# -_-V1.net
KiCad netlist of a schematic drawn in Altium Designer
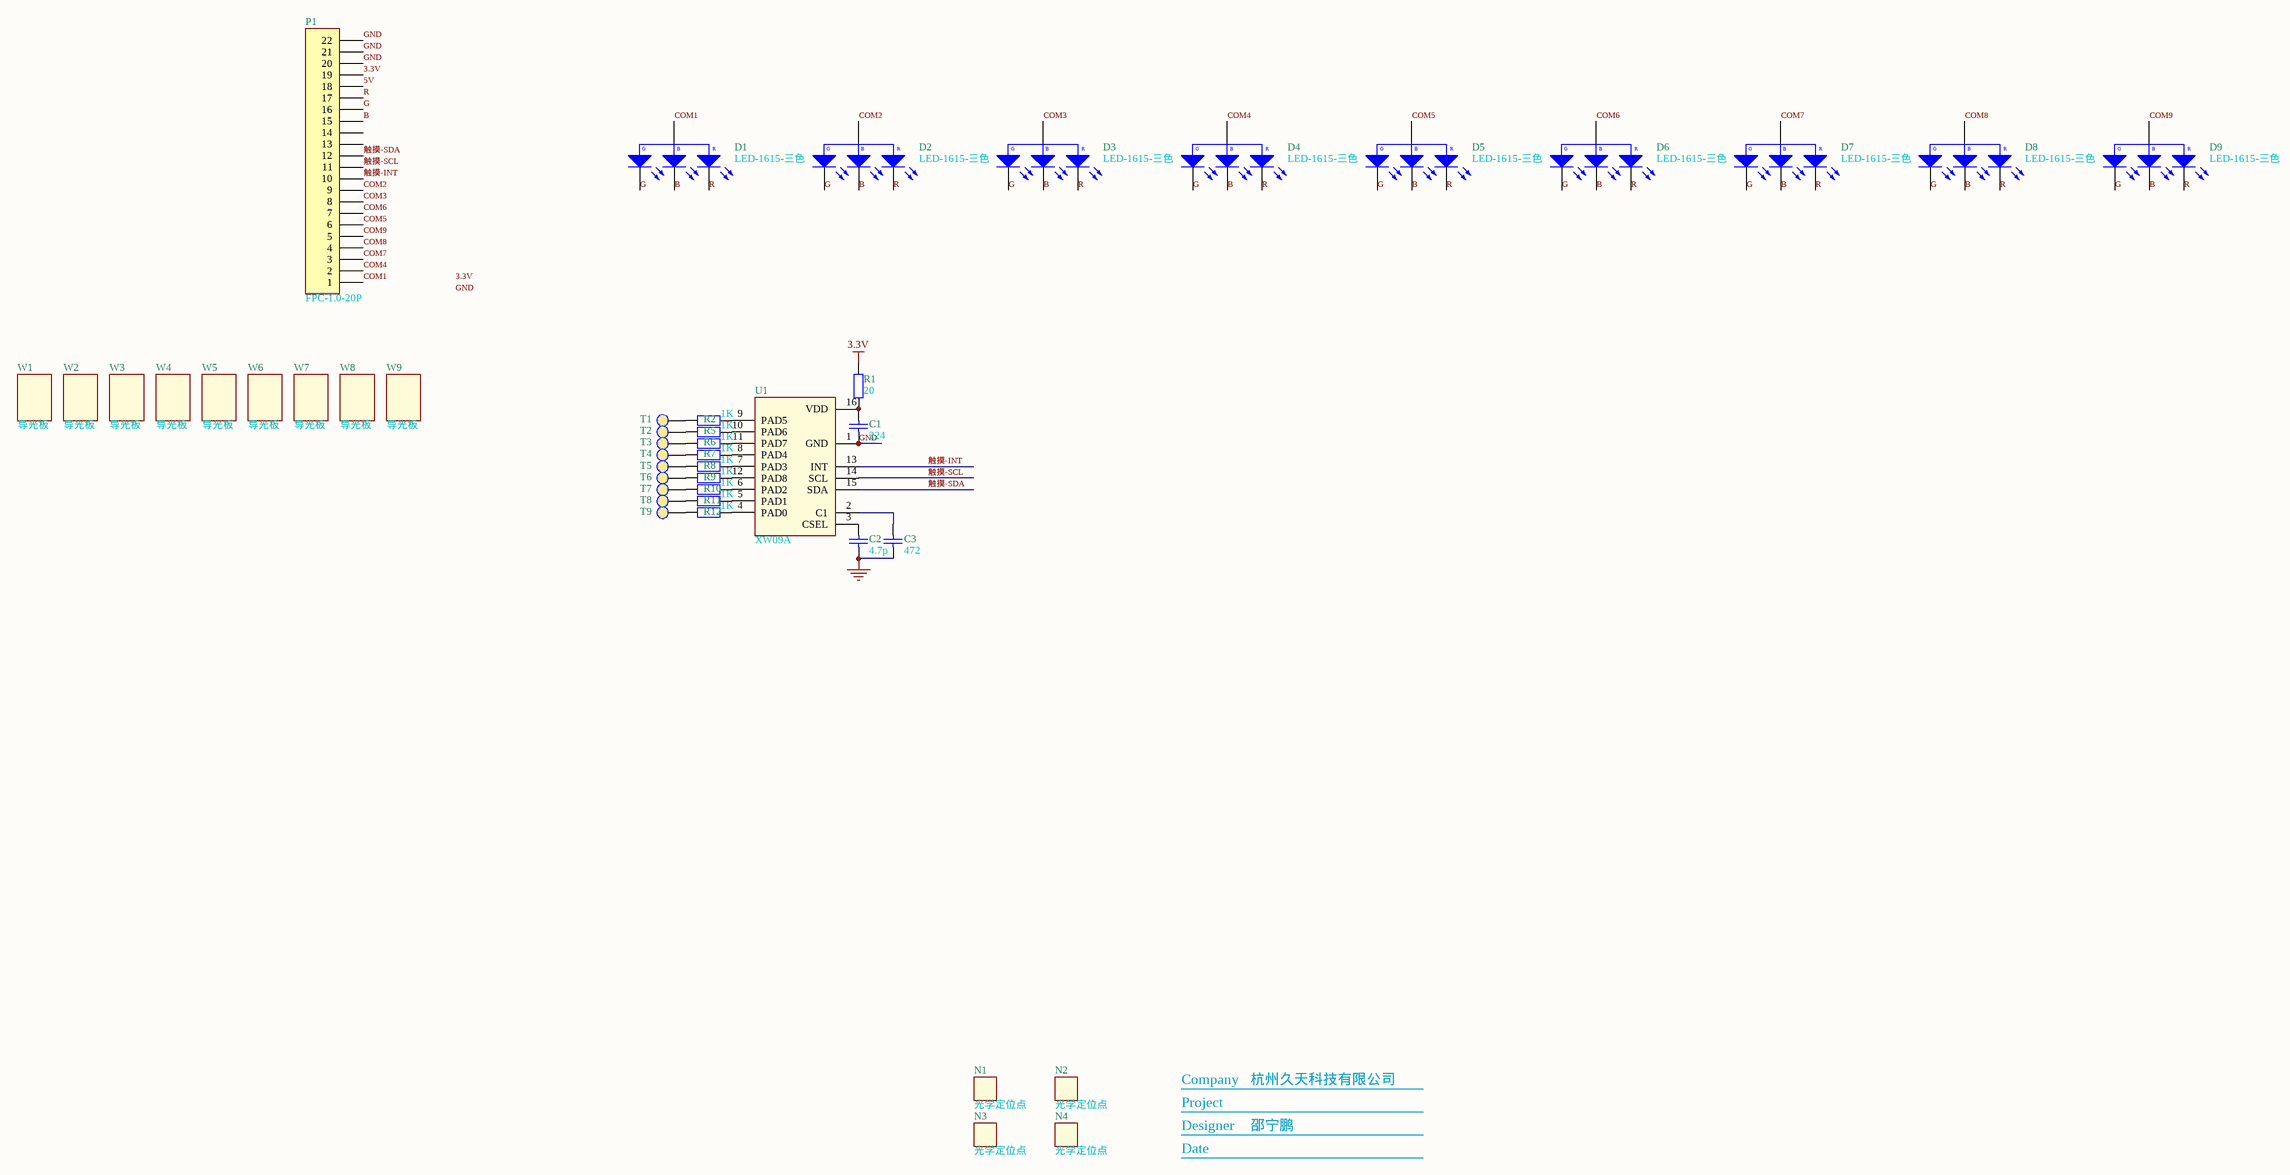
[diagram p0: 九键触摸面板-触摸板-V1.SchDoc]

(export (version "E")
  (design (tool "Eeschema 10.0.6"))
  (components
    (comp (ref "C1")
      (value "224")
      (footprint "C-0603")
      (description "0805")
      (fields (field (name "PUBLISHER") "Altium Limited"))
      (libsource (lib "2电容-V1.0") (part "Cap-0603"))
    )
    (comp (ref "C2")
      (value "4.7p")
      (footprint "C-0603")
      (description "0805")
      (fields (field (name "PUBLISHER") "Altium Limited"))
      (libsource (lib "2电容-V1.0") (part "Cap-0603"))
    )
    (comp (ref "C3")
      (value "472")
      (footprint "C-0603")
      (description "0805")
      (fields (field (name "PUBLISHER") "Altium Limited"))
      (libsource (lib "2电容-V1.0") (part "Cap-0603"))
    )
    (comp (ref "D1")
      (value "LED-1615-三色")
      (footprint "LED-1615-三色")
      (libsource (lib "4二极管-V1.1") (part "LED-1615-三色"))
    )
    (comp (ref "D2")
      (value "LED-1615-三色")
      (footprint "LED-1615-三色")
      (libsource (lib "4二极管-V1.1") (part "LED-1615-三色"))
    )
    (comp (ref "D3")
      (value "LED-1615-三色")
      (footprint "LED-1615-三色")
      (libsource (lib "4二极管-V1.1") (part "LED-1615-三色"))
    )
    (comp (ref "D4")
      (value "LED-1615-三色")
      (footprint "LED-1615-三色")
      (libsource (lib "4二极管-V1.1") (part "LED-1615-三色"))
    )
    (comp (ref "D5")
      (value "LED-1615-三色")
      (footprint "LED-1615-三色")
      (libsource (lib "4二极管-V1.1") (part "LED-1615-三色"))
    )
    (comp (ref "D6")
      (value "LED-1615-三色")
      (footprint "LED-1615-三色")
      (libsource (lib "4二极管-V1.1") (part "LED-1615-三色"))
    )
    (comp (ref "D7")
      (value "LED-1615-三色")
      (footprint "LED-1615-三色")
      (libsource (lib "4二极管-V1.1") (part "LED-1615-三色"))
    )
    (comp (ref "D8")
      (value "LED-1615-三色")
      (footprint "LED-1615-三色")
      (libsource (lib "4二极管-V1.1") (part "LED-1615-三色"))
    )
    (comp (ref "D9")
      (value "LED-1615-三色")
      (footprint "LED-1615-三色")
      (libsource (lib "4二极管-V1.1") (part "LED-1615-三色"))
    )
    (comp (ref "N1") (value "光学定位点") (footprint "MARK-1mm-3mm") (libsource (lib "11其他元件-V1.0") (part "无引脚")))
    (comp (ref "N2") (value "光学定位点") (footprint "MARK-1mm-3mm") (libsource (lib "11其他元件-V1.0") (part "无引脚")))
    (comp (ref "N3") (value "光学定位点") (footprint "MARK-1mm-3mm") (libsource (lib "11其他元件-V1.0") (part "无引脚")))
    (comp (ref "N4") (value "光学定位点") (footprint "MARK-1mm-3mm") (libsource (lib "11其他元件-V1.0") (part "无引脚")))
    (comp (ref "P1")
      (value "FPC-1.0-20P")
      (footprint "FPC-1.0mm_20P下接翻盖")
      (description "Header, 22-Pin")
      (fields (field (name "PUBLISHER") "Altium Limited"))
      (libsource (lib "5排针-V1.0") (part "Header 22"))
    )
    (comp (ref "R1")
      (value "20")
      (footprint "R-0603")
      (description "0603")
      (fields (field (name "PUBLISHER") "Altium Limited"))
      (libsource (lib "") (part "Res2-0603_1"))
    )
    (comp (ref "R2")
      (value "1K")
      (footprint "R-0603")
      (description "0603")
      (fields (field (name "PUBLISHER") "Altium Limited"))
      (libsource (lib "1电阻-V1.0") (part "Res2-0603"))
    )
    (comp (ref "R5")
      (value "1K")
      (footprint "R-0603")
      (description "0603")
      (fields (field (name "PUBLISHER") "Altium Limited"))
      (libsource (lib "1电阻-V1.0") (part "Res2-0603"))
    )
    (comp (ref "R6")
      (value "1K")
      (footprint "R-0603")
      (description "0603")
      (fields (field (name "PUBLISHER") "Altium Limited"))
      (libsource (lib "1电阻-V1.0") (part "Res2-0603"))
    )
    (comp (ref "R7")
      (value "1K")
      (footprint "R-0603")
      (description "0603")
      (fields (field (name "PUBLISHER") "Altium Limited"))
      (libsource (lib "1电阻-V1.0") (part "Res2-0603"))
    )
    (comp (ref "R8")
      (value "1K")
      (footprint "R-0603")
      (description "0603")
      (fields (field (name "PUBLISHER") "Altium Limited"))
      (libsource (lib "1电阻-V1.0") (part "Res2-0603"))
    )
    (comp (ref "R9")
      (value "1K")
      (footprint "R-0603")
      (description "0603")
      (fields (field (name "PUBLISHER") "Altium Limited"))
      (libsource (lib "1电阻-V1.0") (part "Res2-0603"))
    )
    (comp (ref "R10")
      (value "1K")
      (footprint "R-0603")
      (description "0603")
      (fields (field (name "PUBLISHER") "Altium Limited"))
      (libsource (lib "1电阻-V1.0") (part "Res2-0603"))
    )
    (comp (ref "R11")
      (value "1K")
      (footprint "R-0603")
      (description "0603")
      (fields (field (name "PUBLISHER") "Altium Limited"))
      (libsource (lib "1电阻-V1.0") (part "Res2-0603"))
    )
    (comp (ref "R12")
      (value "1K")
      (footprint "R-0603")
      (description "0603")
      (fields (field (name "PUBLISHER") "Altium Limited"))
      (libsource (lib "1电阻-V1.0") (part "Res2-0603"))
    )
    (comp (ref "T1") (value "~") (footprint "焊点1mm") (libsource (lib "11其他元件-V1.0") (part "测试点")))
    (comp (ref "T2") (value "~") (footprint "焊点1mm") (libsource (lib "11其他元件-V1.0") (part "测试点")))
    (comp (ref "T3") (value "~") (footprint "焊点1mm") (libsource (lib "11其他元件-V1.0") (part "测试点")))
    (comp (ref "T4") (value "~") (footprint "焊点1mm") (libsource (lib "11其他元件-V1.0") (part "测试点")))
    (comp (ref "T5") (value "~") (footprint "焊点1mm") (libsource (lib "11其他元件-V1.0") (part "测试点")))
    (comp (ref "T6") (value "~") (footprint "焊点1mm") (libsource (lib "11其他元件-V1.0") (part "测试点")))
    (comp (ref "T7") (value "~") (footprint "焊点1mm") (libsource (lib "11其他元件-V1.0") (part "测试点")))
    (comp (ref "T8") (value "~") (footprint "焊点1mm") (libsource (lib "11其他元件-V1.0") (part "测试点")))
    (comp (ref "T9") (value "~") (footprint "焊点1mm") (libsource (lib "11其他元件-V1.0") (part "测试点")))
    (comp (ref "U1") (value "XW09A") (footprint "SOP-16-M") (libsource (lib "触摸-V1") (part "XW09A")))
    (comp (ref "W1") (value "导光板") (footprint "导光板20.5*15*2") (libsource (lib "11其他元件-V1.0") (part "导光板")))
    (comp (ref "W2") (value "导光板") (footprint "导光板20.5*15*2") (libsource (lib "11其他元件-V1.0") (part "导光板")))
    (comp (ref "W3") (value "导光板") (footprint "导光板20.5*15*2") (libsource (lib "11其他元件-V1.0") (part "导光板")))
    (comp (ref "W4") (value "导光板") (footprint "导光板20.5*15*2") (libsource (lib "11其他元件-V1.0") (part "导光板")))
    (comp (ref "W5") (value "导光板") (footprint "导光板20.5*15*2") (libsource (lib "11其他元件-V1.0") (part "导光板")))
    (comp (ref "W6") (value "导光板") (footprint "导光板20.5*15*2") (libsource (lib "11其他元件-V1.0") (part "导光板")))
    (comp (ref "W7") (value "导光板") (footprint "导光板20.5*15*2") (libsource (lib "11其他元件-V1.0") (part "导光板")))
    (comp (ref "W8") (value "导光板") (footprint "导光板20.5*15*2") (libsource (lib "11其他元件-V1.0") (part "导光板")))
    (comp (ref "W9") (value "导光板") (footprint "导光板20.5*15*2") (libsource (lib "11其他元件-V1.0") (part "导光板")))
  )
  (nets
    (net (code "1") (name "/5V") (class "Default")
      (node (ref "P1") (pin "18") (pinfunction "18_18") (pintype "passive"))
    )
    (net (code "2") (name "/B") (class "Default")
      (node (ref "D1") (pin "4") (pinfunction "G_4") (pintype "passive"))
      (node (ref "D2") (pin "4") (pinfunction "G_4") (pintype "passive"))
      (node (ref "D3") (pin "4") (pinfunction "G_4") (pintype "passive"))
      (node (ref "D4") (pin "4") (pinfunction "G_4") (pintype "passive"))
      (node (ref "D5") (pin "4") (pinfunction "G_4") (pintype "passive"))
      (node (ref "D6") (pin "4") (pinfunction "G_4") (pintype "passive"))
      (node (ref "D7") (pin "4") (pinfunction "G_4") (pintype "passive"))
      (node (ref "D8") (pin "4") (pinfunction "G_4") (pintype "passive"))
      (node (ref "D9") (pin "4") (pinfunction "G_4") (pintype "passive"))
      (node (ref "P1") (pin "15") (pinfunction "15_15") (pintype "passive"))
    )
    (net (code "3") (name "/COM1") (class "Default")
      (node (ref "D1") (pin "2") (pinfunction "A_2") (pintype "passive"))
      (node (ref "P1") (pin "1") (pinfunction "1_1") (pintype "passive"))
    )
    (net (code "4") (name "/COM2") (class "Default")
      (node (ref "D2") (pin "2") (pinfunction "A_2") (pintype "passive"))
      (node (ref "P1") (pin "9") (pinfunction "9_9") (pintype "passive"))
    )
    (net (code "5") (name "/COM3") (class "Default")
      (node (ref "D3") (pin "2") (pinfunction "A_2") (pintype "passive"))
      (node (ref "P1") (pin "8") (pinfunction "8_8") (pintype "passive"))
    )
    (net (code "6") (name "/COM4") (class "Default")
      (node (ref "D4") (pin "2") (pinfunction "A_2") (pintype "passive"))
      (node (ref "P1") (pin "2") (pinfunction "2_2") (pintype "passive"))
    )
    (net (code "7") (name "/COM5") (class "Default")
      (node (ref "D5") (pin "2") (pinfunction "A_2") (pintype "passive"))
      (node (ref "P1") (pin "6") (pinfunction "6_6") (pintype "passive"))
    )
    (net (code "8") (name "/COM6") (class "Default")
      (node (ref "D6") (pin "2") (pinfunction "A_2") (pintype "passive"))
      (node (ref "P1") (pin "7") (pinfunction "7_7") (pintype "passive"))
    )
    (net (code "9") (name "/COM7") (class "Default")
      (node (ref "D7") (pin "2") (pinfunction "A_2") (pintype "passive"))
      (node (ref "P1") (pin "3") (pinfunction "3_3") (pintype "passive"))
    )
    (net (code "10") (name "/COM8") (class "Default")
      (node (ref "D8") (pin "2") (pinfunction "A_2") (pintype "passive"))
      (node (ref "P1") (pin "4") (pinfunction "4_4") (pintype "passive"))
    )
    (net (code "11") (name "/COM9") (class "Default")
      (node (ref "D9") (pin "2") (pinfunction "A_2") (pintype "passive"))
      (node (ref "P1") (pin "5") (pinfunction "5_5") (pintype "passive"))
    )
    (net (code "12") (name "/G") (class "Default")
      (node (ref "D1") (pin "1") (pinfunction "R_1") (pintype "passive"))
      (node (ref "D2") (pin "1") (pinfunction "R_1") (pintype "passive"))
      (node (ref "D3") (pin "1") (pinfunction "R_1") (pintype "passive"))
      (node (ref "D4") (pin "1") (pinfunction "R_1") (pintype "passive"))
      (node (ref "D5") (pin "1") (pinfunction "R_1") (pintype "passive"))
      (node (ref "D6") (pin "1") (pinfunction "R_1") (pintype "passive"))
      (node (ref "D7") (pin "1") (pinfunction "R_1") (pintype "passive"))
      (node (ref "D8") (pin "1") (pinfunction "R_1") (pintype "passive"))
      (node (ref "D9") (pin "1") (pinfunction "R_1") (pintype "passive"))
      (node (ref "P1") (pin "16") (pinfunction "16_16") (pintype "passive"))
    )
    (net (code "13") (name "/R") (class "Default")
      (node (ref "D1") (pin "3") (pinfunction "B_3") (pintype "passive"))
      (node (ref "D2") (pin "3") (pinfunction "B_3") (pintype "passive"))
      (node (ref "D3") (pin "3") (pinfunction "B_3") (pintype "passive"))
      (node (ref "D4") (pin "3") (pinfunction "B_3") (pintype "passive"))
      (node (ref "D5") (pin "3") (pinfunction "B_3") (pintype "passive"))
      (node (ref "D6") (pin "3") (pinfunction "B_3") (pintype "passive"))
      (node (ref "D7") (pin "3") (pinfunction "B_3") (pintype "passive"))
      (node (ref "D8") (pin "3") (pinfunction "B_3") (pintype "passive"))
      (node (ref "D9") (pin "3") (pinfunction "B_3") (pintype "passive"))
      (node (ref "P1") (pin "17") (pinfunction "17_17") (pintype "passive"))
    )
    (net (code "14") (name "/触摸-INT") (class "Default")
      (node (ref "P1") (pin "10") (pinfunction "10_10") (pintype "passive"))
      (node (ref "U1") (pin "13") (pinfunction "INT_13") (pintype "passive"))
    )
    (net (code "15") (name "/触摸-SCL") (class "Default")
      (node (ref "P1") (pin "11") (pinfunction "11_11") (pintype "passive"))
      (node (ref "U1") (pin "14") (pinfunction "SCL_14") (pintype "passive"))
    )
    (net (code "16") (name "/触摸-SDA") (class "Default")
      (node (ref "P1") (pin "12") (pinfunction "12_12") (pintype "passive"))
      (node (ref "U1") (pin "15") (pinfunction "SDA_15") (pintype "passive"))
    )
    (net (code "17") (name "3.3V") (class "Default")
      (node (ref "P1") (pin "19") (pinfunction "19_19") (pintype "passive"))
      (node (ref "R1") (pin "1") (pinfunction "1_1") (pintype "passive"))
    )
    (net (code "18") (name "GND") (class "Default")
      (node (ref "C1") (pin "1") (pinfunction "1_1") (pintype "passive"))
      (node (ref "C2") (pin "1") (pinfunction "1_1") (pintype "passive"))
      (node (ref "C3") (pin "1") (pinfunction "1_1") (pintype "passive"))
      (node (ref "P1") (pin "20") (pinfunction "20_20") (pintype "passive"))
      (node (ref "P1") (pin "21") (pinfunction "21_21") (pintype "passive"))
      (node (ref "P1") (pin "22") (pinfunction "22_22") (pintype "passive"))
      (node (ref "U1") (pin "1") (pinfunction "GND_1") (pintype "passive"))
    )
    (net (code "19") (name "Net-(R2-Pad2)") (class "Default")
      (node (ref "R2") (pin "2") (pinfunction "2_2") (pintype "passive"))
      (node (ref "T1") (pin "1") (pinfunction "1_1") (pintype "passive"))
    )
    (net (code "20") (name "Net-(R5-Pad2)") (class "Default")
      (node (ref "R5") (pin "2") (pinfunction "2_2") (pintype "passive"))
      (node (ref "T2") (pin "1") (pinfunction "1_1") (pintype "passive"))
    )
    (net (code "21") (name "Net-(R6-Pad2)") (class "Default")
      (node (ref "R6") (pin "2") (pinfunction "2_2") (pintype "passive"))
      (node (ref "T3") (pin "1") (pinfunction "1_1") (pintype "passive"))
    )
    (net (code "22") (name "Net-(R7-Pad2)") (class "Default")
      (node (ref "R7") (pin "2") (pinfunction "2_2") (pintype "passive"))
      (node (ref "T4") (pin "1") (pinfunction "1_1") (pintype "passive"))
    )
    (net (code "23") (name "Net-(R8-Pad2)") (class "Default")
      (node (ref "R8") (pin "2") (pinfunction "2_2") (pintype "passive"))
      (node (ref "T5") (pin "1") (pinfunction "1_1") (pintype "passive"))
    )
    (net (code "24") (name "Net-(R9-Pad2)") (class "Default")
      (node (ref "R9") (pin "2") (pinfunction "2_2") (pintype "passive"))
      (node (ref "T6") (pin "1") (pinfunction "1_1") (pintype "passive"))
    )
    (net (code "25") (name "Net-(R10-Pad2)") (class "Default")
      (node (ref "R10") (pin "2") (pinfunction "2_2") (pintype "passive"))
      (node (ref "T7") (pin "1") (pinfunction "1_1") (pintype "passive"))
    )
    (net (code "26") (name "Net-(R11-Pad2)") (class "Default")
      (node (ref "R11") (pin "2") (pinfunction "2_2") (pintype "passive"))
      (node (ref "T8") (pin "1") (pinfunction "1_1") (pintype "passive"))
    )
    (net (code "27") (name "Net-(R12-Pad2)") (class "Default")
      (node (ref "R12") (pin "2") (pinfunction "2_2") (pintype "passive"))
      (node (ref "T9") (pin "1") (pinfunction "1_1") (pintype "passive"))
    )
    (net (code "28") (name "Net-(U1-C1)") (class "Default")
      (node (ref "C3") (pin "2") (pinfunction "2_2") (pintype "passive"))
      (node (ref "U1") (pin "2") (pinfunction "C1_2") (pintype "passive"))
    )
    (net (code "29") (name "Net-(U1-CSEL)") (class "Default")
      (node (ref "C2") (pin "2") (pinfunction "2_2") (pintype "passive"))
      (node (ref "U1") (pin "3") (pinfunction "CSEL_3") (pintype "passive"))
    )
    (net (code "30") (name "Net-(U1-PAD0)") (class "Default")
      (node (ref "R12") (pin "1") (pinfunction "1_1") (pintype "passive"))
      (node (ref "U1") (pin "4") (pinfunction "PAD0_4") (pintype "passive"))
    )
    (net (code "31") (name "Net-(U1-PAD1)") (class "Default")
      (node (ref "R11") (pin "1") (pinfunction "1_1") (pintype "passive"))
      (node (ref "U1") (pin "5") (pinfunction "PAD1_5") (pintype "passive"))
    )
    (net (code "32") (name "Net-(U1-PAD2)") (class "Default")
      (node (ref "R10") (pin "1") (pinfunction "1_1") (pintype "passive"))
      (node (ref "U1") (pin "6") (pinfunction "PAD2_6") (pintype "passive"))
    )
    (net (code "33") (name "Net-(U1-PAD3)") (class "Default")
      (node (ref "R8") (pin "1") (pinfunction "1_1") (pintype "passive"))
      (node (ref "U1") (pin "7") (pinfunction "PAD3_7") (pintype "passive"))
    )
    (net (code "34") (name "Net-(U1-PAD4)") (class "Default")
      (node (ref "R7") (pin "1") (pinfunction "1_1") (pintype "passive"))
      (node (ref "U1") (pin "8") (pinfunction "PAD4_8") (pintype "passive"))
    )
    (net (code "35") (name "Net-(U1-PAD5)") (class "Default")
      (node (ref "R2") (pin "1") (pinfunction "1_1") (pintype "passive"))
      (node (ref "U1") (pin "9") (pinfunction "PAD5_9") (pintype "passive"))
    )
    (net (code "36") (name "Net-(U1-PAD6)") (class "Default")
      (node (ref "R5") (pin "1") (pinfunction "1_1") (pintype "passive"))
      (node (ref "U1") (pin "10") (pinfunction "PAD6_10") (pintype "passive"))
    )
    (net (code "37") (name "Net-(U1-PAD7)") (class "Default")
      (node (ref "R6") (pin "1") (pinfunction "1_1") (pintype "passive"))
      (node (ref "U1") (pin "11") (pinfunction "PAD7_11") (pintype "passive"))
    )
    (net (code "38") (name "Net-(U1-PAD8)") (class "Default")
      (node (ref "R9") (pin "1") (pinfunction "1_1") (pintype "passive"))
      (node (ref "U1") (pin "12") (pinfunction "PAD8_12") (pintype "passive"))
    )
    (net (code "39") (name "Net-(U1-VDD)") (class "Default")
      (node (ref "C1") (pin "2") (pinfunction "2_2") (pintype "passive"))
      (node (ref "R1") (pin "2") (pinfunction "2_2") (pintype "passive"))
      (node (ref "U1") (pin "16") (pinfunction "VDD_16") (pintype "passive"))
    )
    (net (code "40") (name "unconnected-(P1-Pad13)") (class "Default")
      (node (ref "P1") (pin "13") (pinfunction "13_13") (pintype "passive"))
    )
    (net (code "41") (name "unconnected-(P1-Pad14)") (class "Default")
      (node (ref "P1") (pin "14") (pinfunction "14_14") (pintype "passive"))
    )
  )
)
